# MOTOR_SLAVE_BRD_1.net
KiCad netlist of a schematic drawn in EAGLE
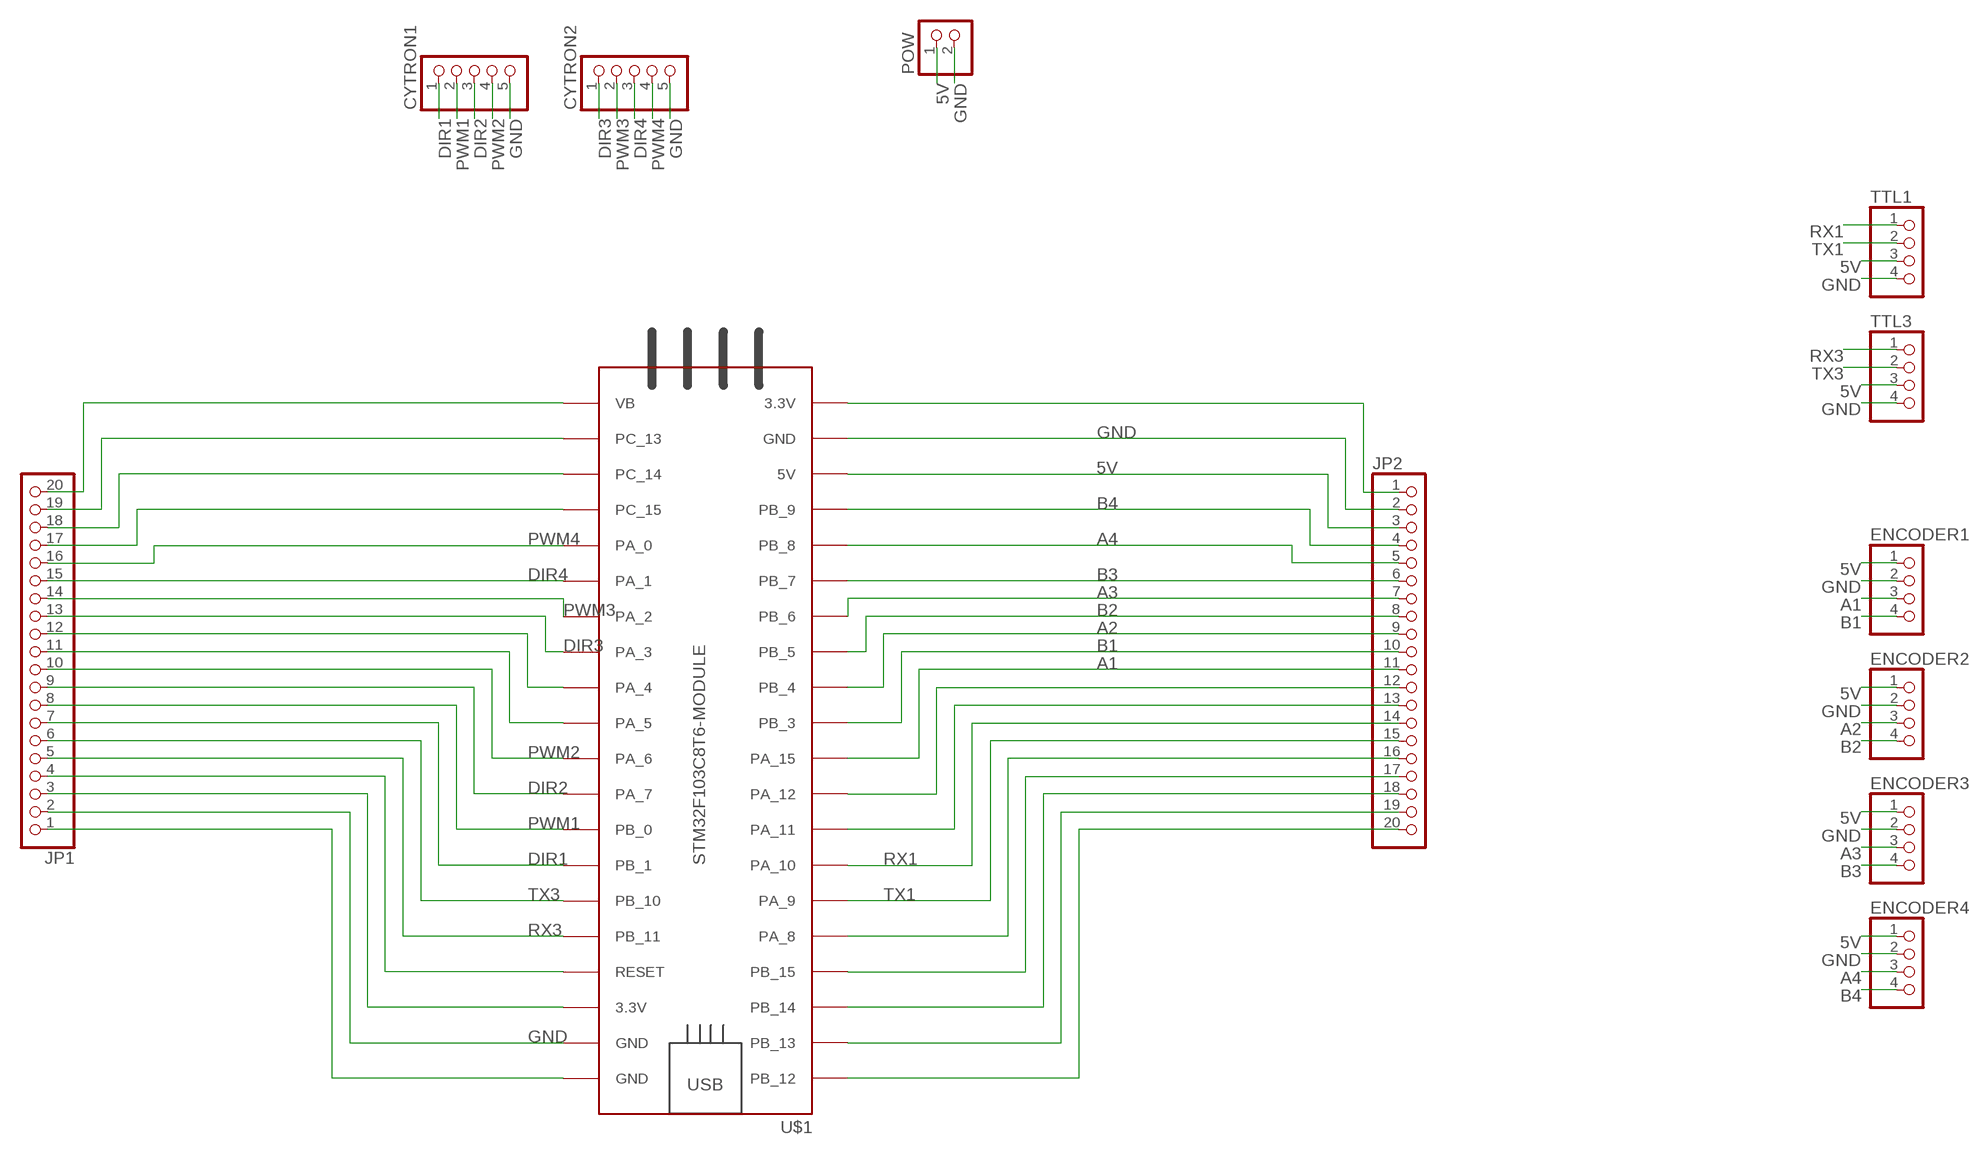
[diagram p0: schematic, sheet 1]

(export (version "E")
  (design (tool "Eeschema 10.0.6"))
  (components
    (comp (ref "CYTRON1")
      (value "PINHD-5_DATA")
      (footprint "eagle-import:1X05_DATA")
      (libsource (lib "eagle-import") (part "PINHD-5_DATA"))
    )
    (comp (ref "CYTRON2")
      (value "PINHD-5_DATA")
      (footprint "eagle-import:1X05_DATA")
      (libsource (lib "eagle-import") (part "PINHD-5_DATA"))
    )
    (comp (ref "ENCODER1")
      (value "PINHD-4_DATA")
      (footprint "eagle-import:1X04_DATA")
      (libsource (lib "eagle-import") (part "PINHD-4_DATA"))
    )
    (comp (ref "ENCODER2")
      (value "PINHD-4_DATA")
      (footprint "eagle-import:1X04_DATA")
      (libsource (lib "eagle-import") (part "PINHD-4_DATA"))
    )
    (comp (ref "ENCODER3")
      (value "PINHD-4_DATA")
      (footprint "eagle-import:1X04_DATA")
      (libsource (lib "eagle-import") (part "PINHD-4_DATA"))
    )
    (comp (ref "ENCODER4")
      (value "PINHD-4_DATA")
      (footprint "eagle-import:1X04_DATA")
      (libsource (lib "eagle-import") (part "PINHD-4_DATA"))
    )
    (comp (ref "JP1")
      (value "PINHD-1X20")
      (footprint "eagle-import:1X20")
      (libsource (lib "eagle-import") (part "PINHD-1X20"))
    )
    (comp (ref "JP2")
      (value "PINHD-1X20")
      (footprint "eagle-import:1X20")
      (libsource (lib "eagle-import") (part "PINHD-1X20"))
    )
    (comp (ref "POW")
      (value "PINHD-2_DATA")
      (footprint "eagle-import:1X02_DATA")
      (libsource (lib "eagle-import") (part "PINHD-2_DATA"))
    )
    (comp (ref "TTL1")
      (value "PINHD-4_DATA")
      (footprint "eagle-import:1X04_DATA")
      (libsource (lib "eagle-import") (part "PINHD-4_DATA"))
    )
    (comp (ref "TTL3")
      (value "PINHD-4_DATA")
      (footprint "eagle-import:1X04_DATA")
      (libsource (lib "eagle-import") (part "PINHD-4_DATA"))
    )
    (comp (ref "U$1")
      (value "STM32F103C8T6-MODULE")
      (footprint "eagle-import:STM32F103C8T6-MODULE")
      (libsource (lib "eagle-import") (part "STM32F103C8T6-MODULE"))
    )
  )
  (nets
    (net (code "1") (name "/5V") (class "Default")
      (node (ref "ENCODER1") (pin "1") (pinfunction "1_1") (pintype "passive"))
      (node (ref "ENCODER2") (pin "1") (pinfunction "1_1") (pintype "passive"))
      (node (ref "ENCODER3") (pin "1") (pinfunction "1_1") (pintype "passive"))
      (node (ref "ENCODER4") (pin "1") (pinfunction "1_1") (pintype "passive"))
      (node (ref "JP2") (pin "3") (pinfunction "3_3") (pintype "passive"))
      (node (ref "POW") (pin "1") (pinfunction "1_1") (pintype "passive"))
      (node (ref "TTL1") (pin "3") (pinfunction "3_3") (pintype "passive"))
      (node (ref "TTL3") (pin "3") (pinfunction "3_3") (pintype "passive"))
      (node (ref "U$1") (pin "5V") (pinfunction "5V_5V") (pintype "bidirectional"))
    )
    (net (code "2") (name "/A1") (class "Default")
      (node (ref "ENCODER1") (pin "3") (pinfunction "3_3") (pintype "passive"))
      (node (ref "JP2") (pin "11") (pinfunction "11_11") (pintype "passive"))
      (node (ref "U$1") (pin "PA_15") (pinfunction "PA_15_PA_15") (pintype "bidirectional"))
    )
    (net (code "3") (name "/A2") (class "Default")
      (node (ref "ENCODER2") (pin "3") (pinfunction "3_3") (pintype "passive"))
      (node (ref "JP2") (pin "9") (pinfunction "9_9") (pintype "passive"))
      (node (ref "U$1") (pin "PB_4") (pinfunction "PB_4_PB_4") (pintype "bidirectional"))
    )
    (net (code "4") (name "/A3") (class "Default")
      (node (ref "ENCODER3") (pin "3") (pinfunction "3_3") (pintype "passive"))
      (node (ref "JP2") (pin "7") (pinfunction "7_7") (pintype "passive"))
      (node (ref "U$1") (pin "PB_6") (pinfunction "PB_6_PB_6") (pintype "bidirectional"))
    )
    (net (code "5") (name "/A4") (class "Default")
      (node (ref "ENCODER4") (pin "3") (pinfunction "3_3") (pintype "passive"))
      (node (ref "JP2") (pin "5") (pinfunction "5_5") (pintype "passive"))
      (node (ref "U$1") (pin "PB_8") (pinfunction "PB_8_PB_8") (pintype "bidirectional"))
    )
    (net (code "6") (name "/B1") (class "Default")
      (node (ref "ENCODER1") (pin "4") (pinfunction "4_4") (pintype "passive"))
      (node (ref "JP2") (pin "10") (pinfunction "10_10") (pintype "passive"))
      (node (ref "U$1") (pin "PB_3") (pinfunction "PB_3_PB_3") (pintype "bidirectional"))
    )
    (net (code "7") (name "/B2") (class "Default")
      (node (ref "ENCODER2") (pin "4") (pinfunction "4_4") (pintype "passive"))
      (node (ref "JP2") (pin "8") (pinfunction "8_8") (pintype "passive"))
      (node (ref "U$1") (pin "PB_5") (pinfunction "PB_5_PB_5") (pintype "bidirectional"))
    )
    (net (code "8") (name "/B3") (class "Default")
      (node (ref "ENCODER3") (pin "4") (pinfunction "4_4") (pintype "passive"))
      (node (ref "JP2") (pin "6") (pinfunction "6_6") (pintype "passive"))
      (node (ref "U$1") (pin "PB_7") (pinfunction "PB_7_PB_7") (pintype "bidirectional"))
    )
    (net (code "9") (name "/B4") (class "Default")
      (node (ref "ENCODER4") (pin "4") (pinfunction "4_4") (pintype "passive"))
      (node (ref "JP2") (pin "4") (pinfunction "4_4") (pintype "passive"))
      (node (ref "U$1") (pin "PB_9") (pinfunction "PB_9_PB_9") (pintype "bidirectional"))
    )
    (net (code "10") (name "/DIR1") (class "Default")
      (node (ref "CYTRON1") (pin "1") (pinfunction "1_1") (pintype "passive"))
      (node (ref "JP1") (pin "7") (pinfunction "7_7") (pintype "passive"))
      (node (ref "U$1") (pin "PB_1") (pinfunction "PB_1_PB_1") (pintype "bidirectional"))
    )
    (net (code "11") (name "/DIR2") (class "Default")
      (node (ref "CYTRON1") (pin "3") (pinfunction "3_3") (pintype "passive"))
      (node (ref "JP1") (pin "9") (pinfunction "9_9") (pintype "passive"))
      (node (ref "U$1") (pin "PA_7") (pinfunction "PA_7_PA_7") (pintype "bidirectional"))
    )
    (net (code "12") (name "/DIR3") (class "Default")
      (node (ref "CYTRON2") (pin "1") (pinfunction "1_1") (pintype "passive"))
      (node (ref "JP1") (pin "13") (pinfunction "13_13") (pintype "passive"))
      (node (ref "U$1") (pin "PA_3") (pinfunction "PA_3_PA_3") (pintype "bidirectional"))
    )
    (net (code "13") (name "/DIR4") (class "Default")
      (node (ref "CYTRON2") (pin "3") (pinfunction "3_3") (pintype "passive"))
      (node (ref "JP1") (pin "15") (pinfunction "15_15") (pintype "passive"))
      (node (ref "U$1") (pin "PA_1") (pinfunction "PA_1_PA_1") (pintype "bidirectional"))
    )
    (net (code "14") (name "/GND") (class "Default")
      (node (ref "CYTRON1") (pin "5") (pinfunction "5_5") (pintype "passive"))
      (node (ref "CYTRON2") (pin "5") (pinfunction "5_5") (pintype "passive"))
      (node (ref "ENCODER1") (pin "2") (pinfunction "2_2") (pintype "passive"))
      (node (ref "ENCODER2") (pin "2") (pinfunction "2_2") (pintype "passive"))
      (node (ref "ENCODER3") (pin "2") (pinfunction "2_2") (pintype "passive"))
      (node (ref "ENCODER4") (pin "2") (pinfunction "2_2") (pintype "passive"))
      (node (ref "JP1") (pin "2") (pinfunction "2_2") (pintype "passive"))
      (node (ref "JP2") (pin "2") (pinfunction "2_2") (pintype "passive"))
      (node (ref "POW") (pin "2") (pinfunction "2_2") (pintype "passive"))
      (node (ref "TTL1") (pin "4") (pinfunction "4_4") (pintype "passive"))
      (node (ref "TTL3") (pin "4") (pinfunction "4_4") (pintype "passive"))
      (node (ref "U$1") (pin "GND_1") (pinfunction "GND_GND_1") (pintype "bidirectional"))
      (node (ref "U$1") (pin "GND_2") (pinfunction "GND_GND_2") (pintype "bidirectional"))
    )
    (net (code "15") (name "/PWM1") (class "Default")
      (node (ref "CYTRON1") (pin "2") (pinfunction "2_2") (pintype "passive"))
      (node (ref "JP1") (pin "8") (pinfunction "8_8") (pintype "passive"))
      (node (ref "U$1") (pin "PB_0") (pinfunction "PB_0_PB_0") (pintype "bidirectional"))
    )
    (net (code "16") (name "/PWM2") (class "Default")
      (node (ref "CYTRON1") (pin "4") (pinfunction "4_4") (pintype "passive"))
      (node (ref "JP1") (pin "10") (pinfunction "10_10") (pintype "passive"))
      (node (ref "U$1") (pin "PA_6") (pinfunction "PA_6_PA_6") (pintype "bidirectional"))
    )
    (net (code "17") (name "/PWM3") (class "Default")
      (node (ref "CYTRON2") (pin "2") (pinfunction "2_2") (pintype "passive"))
      (node (ref "JP1") (pin "14") (pinfunction "14_14") (pintype "passive"))
      (node (ref "U$1") (pin "PA_2") (pinfunction "PA_2_PA_2") (pintype "bidirectional"))
    )
    (net (code "18") (name "/PWM4") (class "Default")
      (node (ref "CYTRON2") (pin "4") (pinfunction "4_4") (pintype "passive"))
      (node (ref "JP1") (pin "16") (pinfunction "16_16") (pintype "passive"))
      (node (ref "U$1") (pin "PA_0") (pinfunction "PA_0_PA_0") (pintype "bidirectional"))
    )
    (net (code "19") (name "/RX1") (class "Default")
      (node (ref "JP2") (pin "14") (pinfunction "14_14") (pintype "passive"))
      (node (ref "TTL1") (pin "1") (pinfunction "1_1") (pintype "passive"))
      (node (ref "U$1") (pin "PA_10") (pinfunction "PA_10_PA_10") (pintype "bidirectional"))
    )
    (net (code "20") (name "/RX3") (class "Default")
      (node (ref "JP1") (pin "5") (pinfunction "5_5") (pintype "passive"))
      (node (ref "TTL3") (pin "1") (pinfunction "1_1") (pintype "passive"))
      (node (ref "U$1") (pin "PB_11") (pinfunction "PB_11_PB_11") (pintype "bidirectional"))
    )
    (net (code "21") (name "/TX1") (class "Default")
      (node (ref "JP2") (pin "15") (pinfunction "15_15") (pintype "passive"))
      (node (ref "TTL1") (pin "2") (pinfunction "2_2") (pintype "passive"))
      (node (ref "U$1") (pin "PA_9") (pinfunction "PA_9_PA_9") (pintype "bidirectional"))
    )
    (net (code "22") (name "/TX3") (class "Default")
      (node (ref "JP1") (pin "6") (pinfunction "6_6") (pintype "passive"))
      (node (ref "TTL3") (pin "2") (pinfunction "2_2") (pintype "passive"))
      (node (ref "U$1") (pin "PB_10") (pinfunction "PB_10_PB_10") (pintype "bidirectional"))
    )
    (net (code "23") (name "Net-(JP1-Pad1)") (class "Default")
      (node (ref "JP1") (pin "1") (pinfunction "1_1") (pintype "passive"))
      (node (ref "U$1") (pin "GND_3") (pinfunction "GND_GND_3") (pintype "power_in"))
    )
    (net (code "24") (name "Net-(JP1-Pad3)") (class "Default")
      (node (ref "JP1") (pin "3") (pinfunction "3_3") (pintype "passive"))
      (node (ref "U$1") (pin "3.3V_2") (pinfunction "3.3V_3.3V_2") (pintype "bidirectional"))
    )
    (net (code "25") (name "Net-(JP1-Pad4)") (class "Default")
      (node (ref "JP1") (pin "4") (pinfunction "4_4") (pintype "passive"))
      (node (ref "U$1") (pin "RESET") (pinfunction "RESET_RESET") (pintype "bidirectional"))
    )
    (net (code "26") (name "Net-(JP1-Pad11)") (class "Default")
      (node (ref "JP1") (pin "11") (pinfunction "11_11") (pintype "passive"))
      (node (ref "U$1") (pin "PA_5") (pinfunction "PA_5_PA_5") (pintype "bidirectional"))
    )
    (net (code "27") (name "Net-(JP1-Pad12)") (class "Default")
      (node (ref "JP1") (pin "12") (pinfunction "12_12") (pintype "passive"))
      (node (ref "U$1") (pin "PA_4") (pinfunction "PA_4_PA_4") (pintype "bidirectional"))
    )
    (net (code "28") (name "Net-(JP1-Pad17)") (class "Default")
      (node (ref "JP1") (pin "17") (pinfunction "17_17") (pintype "passive"))
      (node (ref "U$1") (pin "PC_15") (pinfunction "PC_15_PC_15") (pintype "bidirectional"))
    )
    (net (code "29") (name "Net-(JP1-Pad18)") (class "Default")
      (node (ref "JP1") (pin "18") (pinfunction "18_18") (pintype "passive"))
      (node (ref "U$1") (pin "PC_14") (pinfunction "PC_14_PC_14") (pintype "bidirectional"))
    )
    (net (code "30") (name "Net-(JP1-Pad19)") (class "Default")
      (node (ref "JP1") (pin "19") (pinfunction "19_19") (pintype "passive"))
      (node (ref "U$1") (pin "PC_13") (pinfunction "PC_13_PC_13") (pintype "bidirectional"))
    )
    (net (code "31") (name "Net-(JP1-Pad20)") (class "Default")
      (node (ref "JP1") (pin "20") (pinfunction "20_20") (pintype "passive"))
      (node (ref "U$1") (pin "VB") (pinfunction "VB_VB") (pintype "bidirectional"))
    )
    (net (code "32") (name "Net-(JP2-Pad1)") (class "Default")
      (node (ref "JP2") (pin "1") (pinfunction "1_1") (pintype "passive"))
      (node (ref "U$1") (pin "3.3V_1") (pinfunction "3.3V_3.3V_1") (pintype "bidirectional"))
    )
    (net (code "33") (name "Net-(JP2-Pad12)") (class "Default")
      (node (ref "JP2") (pin "12") (pinfunction "12_12") (pintype "passive"))
      (node (ref "U$1") (pin "PA_12") (pinfunction "PA_12_PA_12") (pintype "bidirectional"))
    )
    (net (code "34") (name "Net-(JP2-Pad13)") (class "Default")
      (node (ref "JP2") (pin "13") (pinfunction "13_13") (pintype "passive"))
      (node (ref "U$1") (pin "PA_11") (pinfunction "PA_11_PA_11") (pintype "bidirectional"))
    )
    (net (code "35") (name "Net-(JP2-Pad16)") (class "Default")
      (node (ref "JP2") (pin "16") (pinfunction "16_16") (pintype "passive"))
      (node (ref "U$1") (pin "PA_8") (pinfunction "PA_8_PA_8") (pintype "bidirectional"))
    )
    (net (code "36") (name "Net-(JP2-Pad17)") (class "Default")
      (node (ref "JP2") (pin "17") (pinfunction "17_17") (pintype "passive"))
      (node (ref "U$1") (pin "PB_15") (pinfunction "PB_15_PB_15") (pintype "bidirectional"))
    )
    (net (code "37") (name "Net-(JP2-Pad18)") (class "Default")
      (node (ref "JP2") (pin "18") (pinfunction "18_18") (pintype "passive"))
      (node (ref "U$1") (pin "PB_14") (pinfunction "PB_14_PB_14") (pintype "bidirectional"))
    )
    (net (code "38") (name "Net-(JP2-Pad19)") (class "Default")
      (node (ref "JP2") (pin "19") (pinfunction "19_19") (pintype "passive"))
      (node (ref "U$1") (pin "PB_13") (pinfunction "PB_13_PB_13") (pintype "bidirectional"))
    )
    (net (code "39") (name "Net-(JP2-Pad20)") (class "Default")
      (node (ref "JP2") (pin "20") (pinfunction "20_20") (pintype "passive"))
      (node (ref "U$1") (pin "PB_12") (pinfunction "PB_12_PB_12") (pintype "bidirectional"))
    )
  )
)
